# Sub-A_BPF.net
KiCad netlist of a schematic drawn in Altium Designer
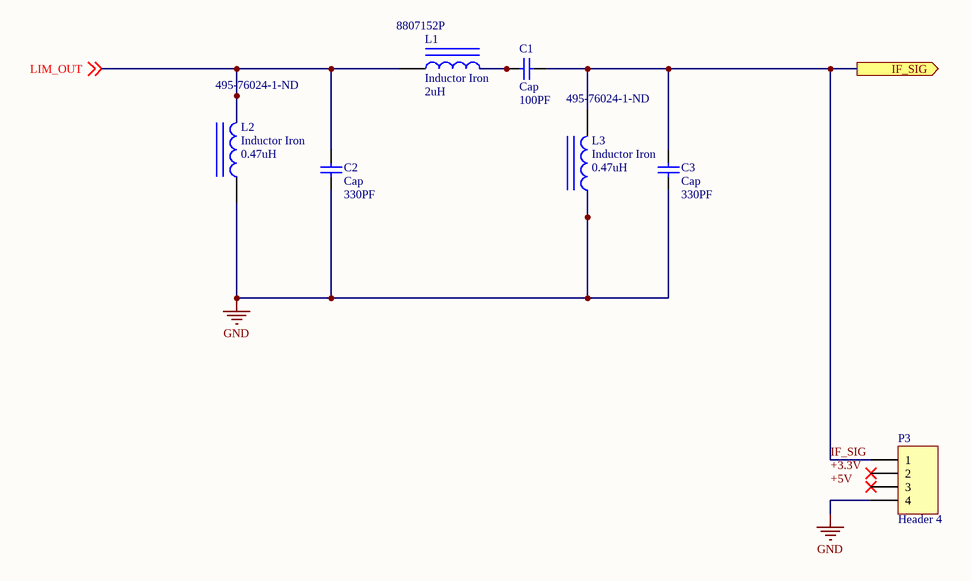
[diagram p0: Sub-A_BPF.SchDoc]

(export (version "E")
  (design (tool "Eeschema 10.0.6"))
  (components
    (comp (ref "C1")
      (value "Cap")
      (footprint "RADIAL-0.1")
      (description "Capacitor")
      (fields
        (field (name "ALTIUM_VALUE") "100PF")
        (field (name "MANUFACTURER PART NUMBER") "K101K15C0GF53L2")
        (field (name "PUBLISHER") "Altium Limited")
      )
      (libsource (lib "ECE295-Capacitors-TH") (part "CAP CER 100PF 50V C0G/NP0 RADIAL"))
    )
    (comp (ref "C2")
      (value "Cap")
      (footprint "RADIAL-0.1")
      (description "Capacitor")
      (fields
        (field (name "ALTIUM_VALUE") "330PF")
        (field (name "MANUFACTURER PART NUMBER") "K331K15X7RF53L2")
        (field (name "PUBLISHER") "Altium Limited")
      )
      (libsource (lib "ECE295-Capacitors-TH") (part "CAP CER 330PF 50V X7R RADIAL"))
    )
    (comp (ref "C3")
      (value "Cap")
      (footprint "RADIAL-0.1")
      (description "Capacitor")
      (fields
        (field (name "ALTIUM_VALUE") "330PF")
        (field (name "MANUFACTURER PART NUMBER") "K331K15X7RF53L2")
        (field (name "PUBLISHER") "Altium Limited")
      )
      (libsource (lib "ECE295-Capacitors-TH") (part "CAP CER 330PF 50V X7R RADIAL"))
    )
    (comp (ref "L1")
      (value "Inductor Iron")
      (footprint "AXIAL-0.9")
      (description "VHF-CHOKE                 2uH      4A")
      (fields
        (field (name "ALTIUM_VALUE") "2uH")
        (field (name "SUPPLIER PART NUMBER 1") "8807152P")
        (field (name "MANUFACTURER") "TDK EPCOS")
        (field (name "MANUFACTURER PART NUMBER") "B82132A5402M")
        (field (name "PUBLISHER") "Altium Limited")
      )
      (libsource (lib "Miscellaneous Devices") (part "Inductor Iron"))
    )
    (comp (ref "L2")
      (value "Inductor Iron")
      (footprint "AXIAL-0.9")
      (description "Fixed Ind 470NH 5A 27 Mohm Th")
      (fields
        (field (name "ALTIUM_VALUE") "0.47uH")
        (field (name "SUPPLIER PART NUMBER 1") "495-76024-1-ND")
        (field (name "MANUFACTURER") "TDK EPCOS")
        (field (name "MANUFACTURER PART NUMBER") "B78108E1471M009")
        (field (name "PUBLISHER") "Altium Limited")
      )
      (libsource (lib "Miscellaneous Devices") (part "Inductor Iron"))
    )
    (comp (ref "L3")
      (value "Inductor Iron")
      (footprint "AXIAL-0.9")
      (description "Fixed Ind 470NH 5A 27 Mohm Th")
      (fields
        (field (name "ALTIUM_VALUE") "0.47uH")
        (field (name "SUPPLIER PART NUMBER 1") "495-76024-1-ND")
        (field (name "MANUFACTURER") "TDK EPCOS")
        (field (name "MANUFACTURER PART NUMBER") "B78108E1471M009")
        (field (name "PUBLISHER") "Altium Limited")
      )
      (libsource (lib "Miscellaneous Devices") (part "Inductor Iron"))
    )
    (comp (ref "P3")
      (value "Header 4")
      (footprint "HDR1X4")
      (description "Header, 4-Pin")
      (fields (field (name "PUBLISHER") "Altium Limited"))
      (libsource (lib "Miscellaneous Connectors") (part "Header 4"))
    )
  )
  (nets
    (net (code "3") (name "/IF_SIG") (class "Default")
      (node (ref "C1") (pin "2") (pinfunction "2_2") (pintype "passive"))
      (node (ref "C3") (pin "2") (pinfunction "2_2") (pintype "passive"))
      (node (ref "L3") (pin "2") (pinfunction "2_2") (pintype "passive"))
      (node (ref "P3") (pin "1") (pinfunction "1_1") (pintype "passive"))
    )
    (net (code "4") (name "GND") (class "Default")
      (node (ref "C2") (pin "1") (pinfunction "1_1") (pintype "passive"))
      (node (ref "C3") (pin "1") (pinfunction "1_1") (pintype "passive"))
      (node (ref "L2") (pin "1") (pinfunction "1_1") (pintype "passive"))
      (node (ref "L3") (pin "1") (pinfunction "1_1") (pintype "passive"))
      (node (ref "P3") (pin "4") (pinfunction "4_4") (pintype "passive"))
    )
    (net (code "5") (name "LIM_OUT") (class "Default")
      (node (ref "C2") (pin "2") (pinfunction "2_2") (pintype "passive"))
      (node (ref "L1") (pin "1") (pinfunction "1_1") (pintype "passive"))
      (node (ref "L2") (pin "2") (pinfunction "2_2") (pintype "passive"))
    )
    (net (code "6") (name "Net-(C1-Pad1)") (class "Default")
      (node (ref "C1") (pin "1") (pinfunction "1_1") (pintype "passive"))
      (node (ref "L1") (pin "2") (pinfunction "2_2") (pintype "passive"))
    )
    (net (code "7") (name "unconnected-(P3-Pad2)") (class "Default")
      (node (ref "P3") (pin "2") (pinfunction "2_2") (pintype "passive+no_connect"))
    )
    (net (code "8") (name "unconnected-(P3-Pad3)") (class "Default")
      (node (ref "P3") (pin "3") (pinfunction "3_3") (pintype "passive+no_connect"))
    )
  )
)
